# power.net
KiCad netlist of a schematic drawn in EAGLE
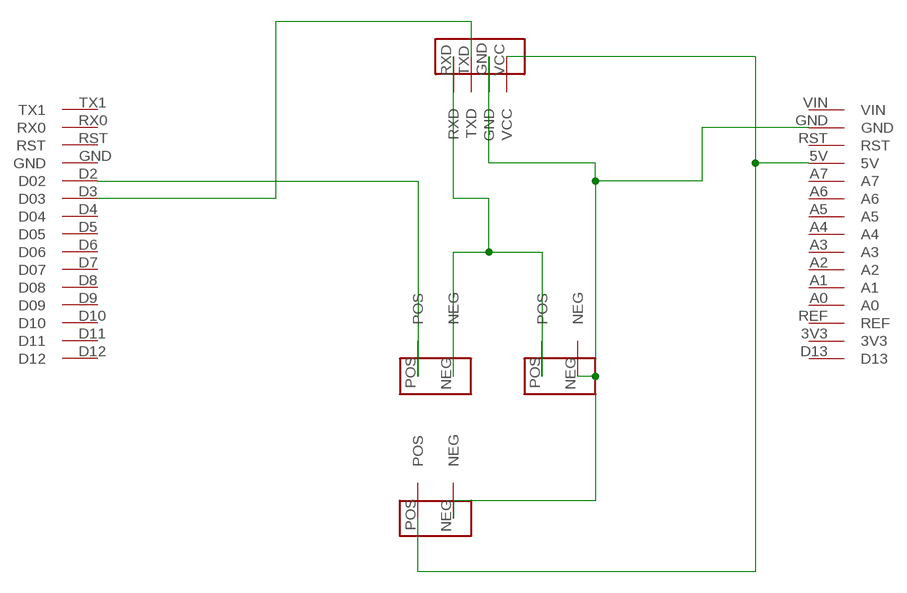
[diagram p0: schematic, sheet 1]

(export (version "E")
  (design (tool "Eeschema 10.0.6"))
  (components
    (comp (ref "POWER")
      (value "CAP")
      (footprint "eagle-import:CAP")
      (libsource (lib "eagle-import") (part "CAP"))
    )
    (comp (ref "U$1")
      (value "ARDUINO-NANO-JUMPER-1")
      (footprint "eagle-import:ARDUINO-NANO-JUMPER-1")
      (libsource (lib "eagle-import") (part "ARDUINO-NANO-JUMPER-1"))
    )
    (comp (ref "U$2")
      (value "ARDUINO-NANO-JUMPER-2")
      (footprint "eagle-import:ARDUINO-NANO-JUMPER-2")
      (libsource (lib "eagle-import") (part "ARDUINO-NANO-JUMPER-2"))
    )
    (comp (ref "U$3")
      (value "RESISTOR")
      (footprint "eagle-import:RESISTOR")
      (libsource (lib "eagle-import") (part "RESISTOR"))
    )
    (comp (ref "U$4")
      (value "RESISTOR")
      (footprint "eagle-import:RESISTOR")
      (libsource (lib "eagle-import") (part "RESISTOR"))
    )
    (comp (ref "U$6") (value "BT") (footprint "eagle-import:BT") (libsource (lib "eagle-import") (part "BT")))
  )
  (nets
    (net (code "1") (name "Net-(POWER-PadNEG)") (class "Default")
      (node (ref "POWER") (pin "NEG") (pinfunction "NEG_NEG") (pintype "bidirectional"))
      (node (ref "U$2") (pin "GND") (pinfunction "GND_GND") (pintype "bidirectional"))
      (node (ref "U$4") (pin "NEG") (pinfunction "NEG_NEG") (pintype "bidirectional"))
      (node (ref "U$6") (pin "GND") (pinfunction "GND_GND") (pintype "bidirectional"))
    )
    (net (code "2") (name "Net-(POWER-PadPOS)") (class "Default")
      (node (ref "POWER") (pin "POS") (pinfunction "POS_POS") (pintype "bidirectional"))
      (node (ref "U$2") (pin "5V") (pinfunction "5V_5V") (pintype "bidirectional"))
      (node (ref "U$6") (pin "VCC") (pinfunction "VCC_VCC") (pintype "bidirectional"))
    )
    (net (code "3") (name "Net-(U$1-D02)") (class "Default")
      (node (ref "U$1") (pin "D2") (pinfunction "D02_D2") (pintype "bidirectional"))
      (node (ref "U$3") (pin "POS") (pinfunction "POS_POS") (pintype "bidirectional"))
    )
    (net (code "4") (name "Net-(U$1-D03)") (class "Default")
      (node (ref "U$1") (pin "D3") (pinfunction "D03_D3") (pintype "bidirectional"))
      (node (ref "U$6") (pin "TXD") (pinfunction "TXD_TXD") (pintype "bidirectional"))
    )
    (net (code "5") (name "Net-(U$3-PadNEG)") (class "Default")
      (node (ref "U$3") (pin "NEG") (pinfunction "NEG_NEG") (pintype "bidirectional"))
      (node (ref "U$4") (pin "POS") (pinfunction "POS_POS") (pintype "bidirectional"))
      (node (ref "U$6") (pin "RXD") (pinfunction "RXD_RXD") (pintype "bidirectional"))
    )
    (net (code "6") (name "unconnected-(U$1-D04-PadD4)") (class "Default")
      (node (ref "U$1") (pin "D4") (pinfunction "D04_D4") (pintype "bidirectional"))
    )
    (net (code "7") (name "unconnected-(U$1-D05-PadD5)") (class "Default")
      (node (ref "U$1") (pin "D5") (pinfunction "D05_D5") (pintype "bidirectional"))
    )
    (net (code "8") (name "unconnected-(U$1-D06-PadD6)") (class "Default")
      (node (ref "U$1") (pin "D6") (pinfunction "D06_D6") (pintype "bidirectional"))
    )
    (net (code "9") (name "unconnected-(U$1-D07-PadD7)") (class "Default")
      (node (ref "U$1") (pin "D7") (pinfunction "D07_D7") (pintype "bidirectional"))
    )
    (net (code "10") (name "unconnected-(U$1-D08-PadD8)") (class "Default")
      (node (ref "U$1") (pin "D8") (pinfunction "D08_D8") (pintype "bidirectional"))
    )
    (net (code "11") (name "unconnected-(U$1-D09-PadD9)") (class "Default")
      (node (ref "U$1") (pin "D9") (pinfunction "D09_D9") (pintype "bidirectional"))
    )
    (net (code "12") (name "unconnected-(U$1-PadD10)") (class "Default")
      (node (ref "U$1") (pin "D10") (pinfunction "D10_D10") (pintype "bidirectional"))
    )
    (net (code "13") (name "unconnected-(U$1-PadD11)") (class "Default")
      (node (ref "U$1") (pin "D11") (pinfunction "D11_D11") (pintype "bidirectional"))
    )
    (net (code "14") (name "unconnected-(U$1-PadD12)") (class "Default")
      (node (ref "U$1") (pin "D12") (pinfunction "D12_D12") (pintype "bidirectional"))
    )
    (net (code "15") (name "unconnected-(U$1-PadGND)") (class "Default")
      (node (ref "U$1") (pin "GND") (pinfunction "GND_GND") (pintype "bidirectional"))
    )
    (net (code "16") (name "unconnected-(U$1-PadRST)") (class "Default")
      (node (ref "U$1") (pin "RST") (pinfunction "RST_RST") (pintype "bidirectional"))
    )
    (net (code "17") (name "unconnected-(U$1-PadRX0)") (class "Default")
      (node (ref "U$1") (pin "RX0") (pinfunction "RX0_RX0") (pintype "bidirectional"))
    )
    (net (code "18") (name "unconnected-(U$1-PadTX1)") (class "Default")
      (node (ref "U$1") (pin "TX1") (pinfunction "TX1_TX1") (pintype "bidirectional"))
    )
    (net (code "19") (name "unconnected-(U$2-Pad3V3)") (class "Default")
      (node (ref "U$2") (pin "3V3") (pinfunction "3V3_3V3") (pintype "bidirectional"))
    )
    (net (code "20") (name "unconnected-(U$2-PadA0)") (class "Default")
      (node (ref "U$2") (pin "A0") (pinfunction "A0_A0") (pintype "bidirectional"))
    )
    (net (code "21") (name "unconnected-(U$2-PadA1)") (class "Default")
      (node (ref "U$2") (pin "A1") (pinfunction "A1_A1") (pintype "bidirectional"))
    )
    (net (code "22") (name "unconnected-(U$2-PadA2)") (class "Default")
      (node (ref "U$2") (pin "A2") (pinfunction "A2_A2") (pintype "bidirectional"))
    )
    (net (code "23") (name "unconnected-(U$2-PadA3)") (class "Default")
      (node (ref "U$2") (pin "A3") (pinfunction "A3_A3") (pintype "bidirectional"))
    )
    (net (code "24") (name "unconnected-(U$2-PadA4)") (class "Default")
      (node (ref "U$2") (pin "A4") (pinfunction "A4_A4") (pintype "bidirectional"))
    )
    (net (code "25") (name "unconnected-(U$2-PadA5)") (class "Default")
      (node (ref "U$2") (pin "A5") (pinfunction "A5_A5") (pintype "bidirectional"))
    )
    (net (code "26") (name "unconnected-(U$2-PadA6)") (class "Default")
      (node (ref "U$2") (pin "A6") (pinfunction "A6_A6") (pintype "bidirectional"))
    )
    (net (code "27") (name "unconnected-(U$2-PadA7)") (class "Default")
      (node (ref "U$2") (pin "A7") (pinfunction "A7_A7") (pintype "bidirectional"))
    )
    (net (code "28") (name "unconnected-(U$2-PadD13)") (class "Default")
      (node (ref "U$2") (pin "D13") (pinfunction "D13_D13") (pintype "bidirectional"))
    )
    (net (code "29") (name "unconnected-(U$2-PadREF)") (class "Default")
      (node (ref "U$2") (pin "REF") (pinfunction "REF_REF") (pintype "bidirectional"))
    )
    (net (code "30") (name "unconnected-(U$2-PadRST)") (class "Default")
      (node (ref "U$2") (pin "RST") (pinfunction "RST_RST") (pintype "bidirectional"))
    )
    (net (code "31") (name "unconnected-(U$2-PadVIN)") (class "Default")
      (node (ref "U$2") (pin "VIN") (pinfunction "VIN_VIN") (pintype "bidirectional"))
    )
  )
)
